# Sch_pwr.net
KiCad netlist of a schematic drawn in Altium Designer
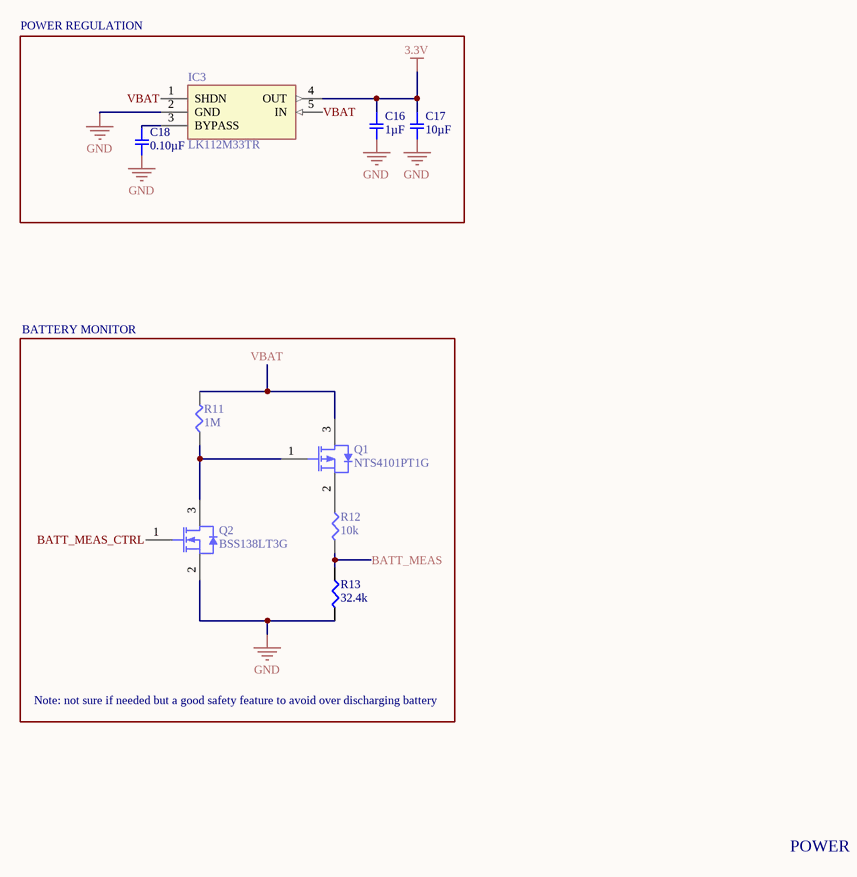
[diagram p0: Sch_pwr.SchDoc]

(export (version "E")
  (design (tool "Eeschema 10.0.6"))
  (components
    (comp (ref "C16")
      (value "1µF")
      (footprint "SMD-0402C")
      (description "CAP CER 1UF 10V X7S 0402")
      (fields
        (field (name "DIGI-KEY PART NUMBER") "490-13409-1-ND")
        (field (name "PART NUMBER") "GCM155C71A105KE38D")
      )
      (libsource (lib "capacitor_murata_0402") (part "GCM155C71A105KE38D"))
    )
    (comp (ref "C17")
      (value "10µF")
      (footprint "SMD-0402C")
      (description "CAP CER 10UF 6.3V X5R 0402")
      (fields
        (field (name "DIGI-KEY PART NUMBER") "490-13211-1-ND")
        (field (name "PART NUMBER") "GRJ155R60J106ME11D")
      )
      (libsource (lib "capacitor_murata_0402") (part "GRJ155R60J106ME11D"))
    )
    (comp (ref "C18")
      (value "0.10µF")
      (footprint "SMD-0402C")
      (description "CAP CER 0.1UF 16V X7R 0402")
      (fields
        (field (name "DIGI-KEY PART NUMBER") "490-4759-1-ND")
        (field (name "PART NUMBER") "GCM155R71C104KA55D")
      )
      (libsource (lib "capacitor_murata_0402") (part "GCM155R71C104KA55D"))
    )
    (comp (ref "IC3")
      (value "LK112M33TR")
      (footprint "SamacSys:SOT95P280X145-5N")
      (description "Integrated Circuit")
      (fields (field (name "MOUSER PART NUMBER") "511-LK112M33") (field (name "RS PART NUMBER") "6869013P"))
      (libsource (lib "*") (part "LK112M33TR"))
    )
    (comp (ref "Q1")
      (value "NTS4101PT1G")
      (footprint "ONSC-SOT-323-3-419-04_V")
      (description "Power MOSFET, -20 V, -1.37 A, Single P-Channel, 3-Pin SOT-323, Pb-Free, Tape and Reel")
      (fields (field (name "MANUFACTURER") "On Semiconductor"))
      (libsource (lib "Altium Content Vault") (part "ONSC-PMOS-G1S2D3-3_D"))
    )
    (comp (ref "Q2")
      (value "BSS138LT3G")
      (footprint "ONSC-SOT-23-3-318-08_V")
      (description "Power MOSFET, 200 mA, 50 V, N-Channel, 3-Pin SOT-23, Pb-Free, Tape and Reel")
      (fields (field (name "MANUFACTURER") "On Semiconductor"))
      (libsource (lib "Altium Content Vault") (part "ONSC-NMOS-G1S2D3-3"))
    )
    (comp (ref "R11")
      (value "1M")
      (footprint "SMD-0402-RES")
      (description "RES SMD 1M OHM 5% 1/10W 0402")
      (fields (field (name "PART NUMBER") "ERJ-2GEJ105X") (field (name "DIGI-KEY PART NUMBER") "P1.0MJCT-ND"))
      (libsource (lib "Panasonic_ERJ_0402") (part "ERJ-2GEJ105X"))
    )
    (comp (ref "R12")
      (value "10k")
      (footprint "SMD-0402-RES")
      (description "RES SMD 10K OHM 5% 1/10W 0402")
      (fields (field (name "PART NUMBER") "ERJ-2GEJ103X") (field (name "DIGI-KEY PART NUMBER") "P10KJCT-ND"))
      (libsource (lib "Panasonic_ERJ_0402") (part "ERJ-2GEJ103X"))
    )
    (comp (ref "R13")
      (value "32.4k")
      (footprint "SMD-0402-RES")
      (description "RES SMD 32.4K OHM 1% 1/10W 0402")
      (fields
        (field (name "PART NUMBER") "ERJ-2RKF3242X")
        (field (name "DIGI-KEY PART NUMBER") "P32.4KLCT-ND")
      )
      (libsource (lib "Panasonic_ERJ_0402") (part "ERJ-2RKF3242X"))
    )
  )
  (nets
    (net (code "1") (name "/BATT_MEAS") (class "Default")
      (node (ref "R12") (pin "2") (pinfunction "2_2") (pintype "passive"))
      (node (ref "R13") (pin "1") (pinfunction "1_1") (pintype "passive"))
    )
    (net (code "2") (name "/BATT_MEAS_CTRL") (class "Default")
      (node (ref "Q2") (pin "1") (pinfunction "G_1") (pintype "passive"))
    )
    (net (code "3") (name "/VBAT") (class "Default")
      (node (ref "IC3") (pin "1") (pinfunction "SHDN_1") (pintype "passive"))
      (node (ref "IC3") (pin "5") (pinfunction "IN_5") (pintype "input"))
      (node (ref "Q1") (pin "3") (pinfunction "D_3") (pintype "passive"))
      (node (ref "R11") (pin "2") (pinfunction "2_2") (pintype "passive"))
    )
    (net (code "4") (name "3.3V") (class "Default")
      (node (ref "C16") (pin "1") (pinfunction "1_1") (pintype "passive"))
      (node (ref "C17") (pin "1") (pinfunction "1_1") (pintype "passive"))
      (node (ref "IC3") (pin "4") (pinfunction "OUT_4") (pintype "output"))
    )
    (net (code "5") (name "GND") (class "Default")
      (node (ref "C16") (pin "2") (pinfunction "2_2") (pintype "passive"))
      (node (ref "C17") (pin "2") (pinfunction "2_2") (pintype "passive"))
      (node (ref "C18") (pin "2") (pinfunction "2_2") (pintype "passive"))
      (node (ref "IC3") (pin "2") (pinfunction "GND_2") (pintype "power_in"))
      (node (ref "Q2") (pin "2") (pinfunction "S_2") (pintype "passive"))
      (node (ref "R13") (pin "2") (pinfunction "2_2") (pintype "passive"))
    )
    (net (code "6") (name "Net-(IC3-BYPASS)") (class "Default")
      (node (ref "C18") (pin "1") (pinfunction "1_1") (pintype "passive"))
      (node (ref "IC3") (pin "3") (pinfunction "BYPASS_3") (pintype "passive"))
    )
    (net (code "7") (name "Net-(Q1-G)") (class "Default")
      (node (ref "Q1") (pin "1") (pinfunction "G_1") (pintype "passive"))
      (node (ref "Q2") (pin "3") (pinfunction "D_3") (pintype "passive"))
      (node (ref "R11") (pin "1") (pinfunction "1_1") (pintype "passive"))
    )
    (net (code "8") (name "Net-(Q1-S)") (class "Default")
      (node (ref "Q1") (pin "2") (pinfunction "S_2") (pintype "passive"))
      (node (ref "R12") (pin "1") (pinfunction "1_1") (pintype "passive"))
    )
  )
)
